# backplane_ethernet.net
KiCad netlist of a schematic drawn in Altium Designer
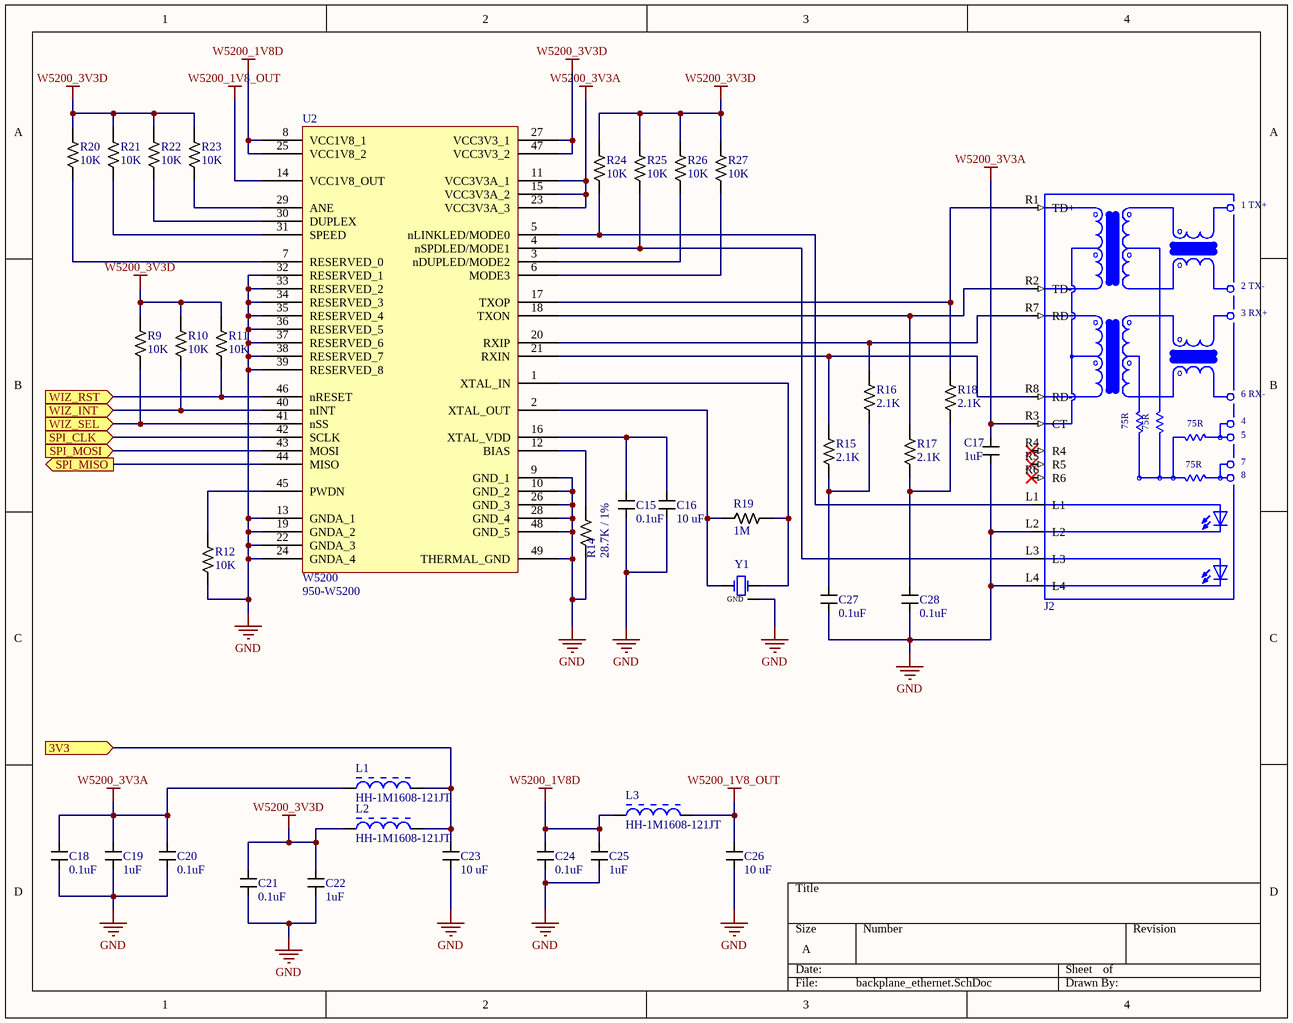
[diagram p0: backplane_ethernet.SchDoc]

(export (version "E")
  (design (tool "Eeschema 10.0.6"))
  (components
    (comp (ref "C15")
      (value "0.1uF")
      (footprint "CAPACITOR_0603")
      (description "Cap 100nF 6.3V +/-10%\r\nCeramic 0603")
      (fields
        (field (name "TOLERANCE") "+/- 10%")
        (field (name "VOLTAGE") "6.3V")
        (field (name "MADE BY") "Flip B")
      )
      (libsource (lib "Capacitors") (part "CAPACITOR_0.1uF_0603"))
    )
    (comp (ref "C16")
      (value "10uF Ceramic 6.3V")
      (footprint "CAPACITOR_0603")
      (description "Cap 10uF 6.3V +/-20%\r\nCeramic 0603")
      (fields
        (field (name "TOLERANCE") "+/- 20%")
        (field (name "VOLTAGE") "6.3V")
        (field (name "VALUE (UF)") "10 uF")
        (field (name "MADE BY") "Flip B")
      )
      (libsource (lib "Capacitors") (part "CAPACITOR_10uF_0603"))
    )
    (comp (ref "C17")
      (value "1uF")
      (footprint "CAPACITOR_0603")
      (description "Cap 1uF 16V +/-10%\r\nCeramic 0603")
      (fields
        (field (name "TOLERANCE") "+/- 10%")
        (field (name "VOLTAGE") "16V")
        (field (name "MADE BY") "Flip B")
      )
      (libsource (lib "Capacitors") (part "CAPACITOR_1uF_0603"))
    )
    (comp (ref "C18")
      (value "0.1uF")
      (footprint "CAPACITOR_0603")
      (description "Cap 100nF 6.3V +/-10%\r\nCeramic 0603")
      (fields
        (field (name "TOLERANCE") "+/- 10%")
        (field (name "VOLTAGE") "6.3V")
        (field (name "MADE BY") "Flip B")
      )
      (libsource (lib "Capacitors") (part "CAPACITOR_0.1uF_0603"))
    )
    (comp (ref "C19")
      (value "1uF")
      (footprint "CAPACITOR_0603")
      (description "Cap 1uF 16V +/-10%\r\nCeramic 0603")
      (fields
        (field (name "TOLERANCE") "+/- 10%")
        (field (name "VOLTAGE") "16V")
        (field (name "MADE BY") "Flip B")
      )
      (libsource (lib "Capacitors") (part "CAPACITOR_1uF_0603"))
    )
    (comp (ref "C20")
      (value "0.1uF")
      (footprint "CAPACITOR_0603")
      (description "Cap 100nF 6.3V +/-10%\r\nCeramic 0603")
      (fields
        (field (name "TOLERANCE") "+/- 10%")
        (field (name "VOLTAGE") "6.3V")
        (field (name "MADE BY") "Flip B")
      )
      (libsource (lib "Capacitors") (part "CAPACITOR_0.1uF_0603"))
    )
    (comp (ref "C21")
      (value "0.1uF")
      (footprint "CAPACITOR_0603")
      (description "Cap 100nF 6.3V +/-10%\r\nCeramic 0603")
      (fields
        (field (name "TOLERANCE") "+/- 10%")
        (field (name "VOLTAGE") "6.3V")
        (field (name "MADE BY") "Flip B")
      )
      (libsource (lib "Capacitors") (part "CAPACITOR_0.1uF_0603"))
    )
    (comp (ref "C22")
      (value "1uF")
      (footprint "CAPACITOR_0603")
      (description "Cap 1uF 16V +/-10%\r\nCeramic 0603")
      (fields
        (field (name "TOLERANCE") "+/- 10%")
        (field (name "VOLTAGE") "16V")
        (field (name "MADE BY") "Flip B")
      )
      (libsource (lib "Capacitors") (part "CAPACITOR_1uF_0603"))
    )
    (comp (ref "C23")
      (value "10uF Ceramic 6.3V")
      (footprint "CAPACITOR_0603")
      (description "Cap 10uF 6.3V +/-20%\r\nCeramic 0603")
      (fields
        (field (name "TOLERANCE") "+/- 20%")
        (field (name "VOLTAGE") "6.3V")
        (field (name "VALUE (UF)") "10 uF")
        (field (name "MADE BY") "Flip B")
      )
      (libsource (lib "Capacitors") (part "CAPACITOR_10uF_0603"))
    )
    (comp (ref "C24")
      (value "0.1uF")
      (footprint "CAPACITOR_0603")
      (description "Cap 100nF 6.3V +/-10%\r\nCeramic 0603")
      (fields
        (field (name "TOLERANCE") "+/- 10%")
        (field (name "VOLTAGE") "6.3V")
        (field (name "MADE BY") "Flip B")
      )
      (libsource (lib "Capacitors") (part "CAPACITOR_0.1uF_0603"))
    )
    (comp (ref "C25")
      (value "1uF")
      (footprint "CAPACITOR_0603")
      (description "Cap 1uF 16V +/-10%\r\nCeramic 0603")
      (fields
        (field (name "TOLERANCE") "+/- 10%")
        (field (name "VOLTAGE") "16V")
        (field (name "MADE BY") "Flip B")
      )
      (libsource (lib "Capacitors") (part "CAPACITOR_1uF_0603"))
    )
    (comp (ref "C26")
      (value "10uF Ceramic 6.3V")
      (footprint "CAPACITOR_0603")
      (description "Cap 10uF 6.3V +/-20%\r\nCeramic 0603")
      (fields
        (field (name "TOLERANCE") "+/- 20%")
        (field (name "VOLTAGE") "6.3V")
        (field (name "VALUE (UF)") "10 uF")
        (field (name "MADE BY") "Flip B")
      )
      (libsource (lib "Capacitors") (part "CAPACITOR_10uF_0603"))
    )
    (comp (ref "C27")
      (value "0.1uF")
      (footprint "CAPACITOR_0603")
      (description "Cap 100nF 6.3V +/-10%\r\nCeramic 0603")
      (fields
        (field (name "TOLERANCE") "+/- 10%")
        (field (name "VOLTAGE") "6.3V")
        (field (name "MADE BY") "Flip B")
      )
      (libsource (lib "Capacitors") (part "CAPACITOR_0.1uF_0603"))
    )
    (comp (ref "C28")
      (value "0.1uF")
      (footprint "CAPACITOR_0603")
      (description "Cap 100nF 6.3V +/-10%\r\nCeramic 0603")
      (fields
        (field (name "TOLERANCE") "+/- 10%")
        (field (name "VOLTAGE") "6.3V")
        (field (name "MADE BY") "Flip B")
      )
      (libsource (lib "Capacitors") (part "CAPACITOR_0.1uF_0603"))
    )
    (comp (ref "J2")
      (value "Ethernet Connector")
      (footprint "WIZNET_RB1-125BAG1A")
      (description "CONN JACK 1PORT 100 BASE-T PCB")
      (libsource (lib "Connectors") (part "RB1-125BAG1A"))
    )
    (comp (ref "L1")
      (value "HH-1M1608-121JT")
      (footprint "CTC-1608_L")
      (description "Chip Ferrite Bead, 0.14 Ohm, 1.1 A, -55 to 125 degC, 2-Pin SMD, RoHS, Tape and Reel")
      (fields (field (name "MANUFACTURER") "CTC Coils") (field (name "PARTNUMBER") "HH-1M1608"))
      (libsource (lib "Altium Content Vault") (part "IND-FB-2"))
    )
    (comp (ref "L2")
      (value "HH-1M1608-121JT")
      (footprint "CTC-1608_L")
      (description "Chip Ferrite Bead, 0.14 Ohm, 1.1 A, -55 to 125 degC, 2-Pin SMD, RoHS, Tape and Reel")
      (fields (field (name "MANUFACTURER") "CTC Coils") (field (name "PARTNUMBER") "HH-1M1608"))
      (libsource (lib "Altium Content Vault") (part "IND-FB-2"))
    )
    (comp (ref "L3")
      (value "HH-1M1608-121JT")
      (footprint "CTC-1608_L")
      (description "Chip Ferrite Bead, 0.14 Ohm, 1.1 A, -55 to 125 degC, 2-Pin SMD, RoHS, Tape and Reel")
      (fields (field (name "MANUFACTURER") "CTC Coils") (field (name "PARTNUMBER") "HH-1M1608"))
      (libsource (lib "Altium Content Vault") (part "IND-FB-2"))
    )
    (comp (ref "R9")
      (value "10k Ohm 5% 1/10W")
      (footprint "RESISTOR_0603")
      (description "RES 10k OHM 5% 1/10W 0603")
      (fields
        (field (name "TOLERANCE") "+/- 5%")
        (field (name "VALUE  (OHMS)") "10K")
        (field (name "MADE BY") "Robert Pafford")
      )
      (libsource (lib "Resistors") (part "RESISTOR_10K_0603"))
    )
    (comp (ref "R10")
      (value "10k Ohm 5% 1/10W")
      (footprint "RESISTOR_0603")
      (description "RES 10k OHM 5% 1/10W 0603")
      (fields
        (field (name "TOLERANCE") "+/- 5%")
        (field (name "VALUE  (OHMS)") "10K")
        (field (name "MADE BY") "Robert Pafford")
      )
      (libsource (lib "Resistors") (part "RESISTOR_10K_0603"))
    )
    (comp (ref "R11")
      (value "10k Ohm 5% 1/10W")
      (footprint "RESISTOR_0603")
      (description "RES 10k OHM 5% 1/10W 0603")
      (fields
        (field (name "TOLERANCE") "+/- 5%")
        (field (name "VALUE  (OHMS)") "10K")
        (field (name "MADE BY") "Robert Pafford")
      )
      (libsource (lib "Resistors") (part "RESISTOR_10K_0603"))
    )
    (comp (ref "R12")
      (value "10k Ohm 5% 1/10W")
      (footprint "RESISTOR_0603")
      (description "RES 10k OHM 5% 1/10W 0603")
      (fields
        (field (name "TOLERANCE") "+/- 5%")
        (field (name "VALUE  (OHMS)") "10K")
        (field (name "MADE BY") "Robert Pafford")
      )
      (libsource (lib "Resistors") (part "RESISTOR_10K_0603"))
    )
    (comp (ref "R14")
      (value "K / 1%")
      (footprint "RESISTOR_0603")
      (description "RES 28.7K OHM 1% 1/8W 0603")
      (fields
        (field (name "TOLERANCE") "+/- 5%")
        (field (name "VALUE  (OHMS)") "28.7K / 1%")
        (field (name "MADE BY") "Robert Pafford")
      )
      (libsource (lib "Resistors") (part "RESISTOR_28.7K / 1%_0603_1"))
    )
    (comp (ref "R15")
      (value "2.1k Ohm 5% 1/8W")
      (footprint "RESISTOR_0603")
      (description "RES 2.1k OHM 5% 1/8W 0603")
      (fields
        (field (name "TOLERANCE") "+/- 5%")
        (field (name "VALUE  (OHMS)") "2.1K")
        (field (name "MADE BY") "Robert Pafford")
      )
      (libsource (lib "Resistors") (part "RESISTOR_2.1K_0603_1"))
    )
    (comp (ref "R16")
      (value "2.1k Ohm 5% 1/8W")
      (footprint "RESISTOR_0603")
      (description "RES 2.1k OHM 5% 1/8W 0603")
      (fields
        (field (name "TOLERANCE") "+/- 5%")
        (field (name "VALUE  (OHMS)") "2.1K")
        (field (name "MADE BY") "Robert Pafford")
      )
      (libsource (lib "Resistors") (part "RESISTOR_2.1K_0603_1"))
    )
    (comp (ref "R17")
      (value "2.1k Ohm 5% 1/8W")
      (footprint "RESISTOR_0603")
      (description "RES 2.1k OHM 5% 1/8W 0603")
      (fields
        (field (name "TOLERANCE") "+/- 5%")
        (field (name "VALUE  (OHMS)") "2.1K")
        (field (name "MADE BY") "Robert Pafford")
      )
      (libsource (lib "Resistors") (part "RESISTOR_2.1K_0603_1"))
    )
    (comp (ref "R18")
      (value "2.1k Ohm 5% 1/8W")
      (footprint "RESISTOR_0603")
      (description "RES 2.1k OHM 5% 1/8W 0603")
      (fields
        (field (name "TOLERANCE") "+/- 5%")
        (field (name "VALUE  (OHMS)") "2.1K")
        (field (name "MADE BY") "Robert Pafford")
      )
      (libsource (lib "Resistors") (part "RESISTOR_2.1K_0603_1"))
    )
    (comp (ref "R19")
      (value "1M")
      (footprint "RESISTOR_0603")
      (description "RES 1M OHM 1/8W 0603")
      (fields
        (field (name "TOLERANCE") "+/- 5%")
        (field (name "VALUE  (OHMS)") "1M")
        (field (name "MADE BY") "Robert Pafford")
      )
      (libsource (lib "Resistors") (part "RESISTOR_1M_0603_1"))
    )
    (comp (ref "R20")
      (value "10k Ohm 5% 1/10W")
      (footprint "RESISTOR_0603")
      (description "RES 10k OHM 5% 1/10W 0603")
      (fields
        (field (name "TOLERANCE") "+/- 5%")
        (field (name "VALUE  (OHMS)") "10K")
        (field (name "MADE BY") "Robert Pafford")
      )
      (libsource (lib "Resistors") (part "RESISTOR_10K_0603"))
    )
    (comp (ref "R21")
      (value "10k Ohm 5% 1/10W")
      (footprint "RESISTOR_0603")
      (description "RES 10k OHM 5% 1/10W 0603")
      (fields
        (field (name "TOLERANCE") "+/- 5%")
        (field (name "VALUE  (OHMS)") "10K")
        (field (name "MADE BY") "Robert Pafford")
      )
      (libsource (lib "Resistors") (part "RESISTOR_10K_0603"))
    )
    (comp (ref "R22")
      (value "10k Ohm 5% 1/10W")
      (footprint "RESISTOR_0603")
      (description "RES 10k OHM 5% 1/10W 0603")
      (fields
        (field (name "TOLERANCE") "+/- 5%")
        (field (name "VALUE  (OHMS)") "10K")
        (field (name "MADE BY") "Robert Pafford")
      )
      (libsource (lib "Resistors") (part "RESISTOR_10K_0603"))
    )
    (comp (ref "R23")
      (value "10k Ohm 5% 1/10W")
      (footprint "RESISTOR_0603")
      (description "RES 10k OHM 5% 1/10W 0603")
      (fields
        (field (name "TOLERANCE") "+/- 5%")
        (field (name "VALUE  (OHMS)") "10K")
        (field (name "MADE BY") "Robert Pafford")
      )
      (libsource (lib "Resistors") (part "RESISTOR_10K_0603"))
    )
    (comp (ref "R24")
      (value "10k Ohm 5% 1/10W")
      (footprint "RESISTOR_0603")
      (description "RES 10k OHM 5% 1/10W 0603")
      (fields
        (field (name "TOLERANCE") "+/- 5%")
        (field (name "VALUE  (OHMS)") "10K")
        (field (name "MADE BY") "Robert Pafford")
      )
      (libsource (lib "Resistors") (part "RESISTOR_10K_0603"))
    )
    (comp (ref "R25")
      (value "10k Ohm 5% 1/10W")
      (footprint "RESISTOR_0603")
      (description "RES 10k OHM 5% 1/10W 0603")
      (fields
        (field (name "TOLERANCE") "+/- 5%")
        (field (name "VALUE  (OHMS)") "10K")
        (field (name "MADE BY") "Robert Pafford")
      )
      (libsource (lib "Resistors") (part "RESISTOR_10K_0603"))
    )
    (comp (ref "R26")
      (value "10k Ohm 5% 1/10W")
      (footprint "RESISTOR_0603")
      (description "RES 10k OHM 5% 1/10W 0603")
      (fields
        (field (name "TOLERANCE") "+/- 5%")
        (field (name "VALUE  (OHMS)") "10K")
        (field (name "MADE BY") "Robert Pafford")
      )
      (libsource (lib "Resistors") (part "RESISTOR_10K_0603"))
    )
    (comp (ref "R27")
      (value "10k Ohm 5% 1/10W")
      (footprint "RESISTOR_0603")
      (description "RES 10k OHM 5% 1/10W 0603")
      (fields
        (field (name "TOLERANCE") "+/- 5%")
        (field (name "VALUE  (OHMS)") "10K")
        (field (name "MADE BY") "Robert Pafford")
      )
      (libsource (lib "Resistors") (part "RESISTOR_10K_0603"))
    )
    (comp (ref "U2")
      (value "W5200")
      (footprint "QFN-48")
      (description "WIZNET W5200\r\n48QFN (7x7 mm)")
      (fields
        (field (name "MF") "Texas Instruments")
        (field (name "MP") "LM1117IMPX-3.3/NOPB")
        (field (name "SUPPLIER PART NUMBER 1") "950-W5200")
        (field (name "CREATED BY:") "Siddharth.V")
      )
      (libsource (lib "Integrated Circuits") (part "W5200"))
    )
    (comp (ref "Y1")
      (value "CRYSTAL 25.0000MHZ 18PF SMD")
      (footprint "4-SMD No Lead Crystal")
      (description "25 MHz ±20ppm Crystal 18pF")
      (fields (field (name "MADE BY") "Robert Pafford"))
      (libsource (lib "Crystals") (part "CRYSTAL_25MHz_SMD_1"))
    )
  )
  (nets
    (net (code "1") (name "/3V3") (class "Default")
      (node (ref "C23") (pin "1") (pinfunction "1_1") (pintype "passive"))
      (node (ref "L1") (pin "2") (pinfunction "2_2") (pintype "passive"))
      (node (ref "L2") (pin "2") (pinfunction "2_2") (pintype "passive"))
    )
    (net (code "2") (name "/SPI_CLK") (class "Default")
      (node (ref "U2") (pin "42") (pinfunction "SCLK_42") (pintype "passive"))
    )
    (net (code "3") (name "/SPI_MISO") (class "Default")
      (node (ref "U2") (pin "44") (pinfunction "MISO_44") (pintype "passive"))
    )
    (net (code "4") (name "/SPI_MOSI") (class "Default")
      (node (ref "U2") (pin "43") (pinfunction "MOSI_43") (pintype "passive"))
    )
    (net (code "5") (name "/WIZ_INT") (class "Default")
      (node (ref "R10") (pin "2") (pinfunction "2_2") (pintype "passive"))
      (node (ref "U2") (pin "40") (pinfunction "nINT_40") (pintype "passive"))
    )
    (net (code "6") (name "/WIZ_RST") (class "Default")
      (node (ref "R11") (pin "2") (pinfunction "2_2") (pintype "passive"))
      (node (ref "U2") (pin "46") (pinfunction "nRESET_46") (pintype "passive"))
    )
    (net (code "7") (name "/WIZ_SEL") (class "Default")
      (node (ref "R9") (pin "2") (pinfunction "2_2") (pintype "passive"))
      (node (ref "U2") (pin "41") (pinfunction "nSS_41") (pintype "passive"))
    )
    (net (code "8") (name "GND") (class "Default")
      (node (ref "C15") (pin "2") (pinfunction "2_2") (pintype "passive"))
      (node (ref "C16") (pin "2") (pinfunction "2_2") (pintype "passive"))
      (node (ref "C17") (pin "2") (pinfunction "2_2") (pintype "passive"))
      (node (ref "C18") (pin "2") (pinfunction "2_2") (pintype "passive"))
      (node (ref "C19") (pin "2") (pinfunction "2_2") (pintype "passive"))
      (node (ref "C20") (pin "2") (pinfunction "2_2") (pintype "passive"))
      (node (ref "C21") (pin "2") (pinfunction "2_2") (pintype "passive"))
      (node (ref "C22") (pin "2") (pinfunction "2_2") (pintype "passive"))
      (node (ref "C23") (pin "2") (pinfunction "2_2") (pintype "passive"))
      (node (ref "C24") (pin "2") (pinfunction "2_2") (pintype "passive"))
      (node (ref "C25") (pin "2") (pinfunction "2_2") (pintype "passive"))
      (node (ref "C26") (pin "2") (pinfunction "2_2") (pintype "passive"))
      (node (ref "C27") (pin "2") (pinfunction "2_2") (pintype "passive"))
      (node (ref "C28") (pin "2") (pinfunction "2_2") (pintype "passive"))
      (node (ref "J2") (pin "L2") (pinfunction "L2_L2") (pintype "passive"))
      (node (ref "J2") (pin "L4") (pinfunction "L4_L4") (pintype "passive"))
      (node (ref "R12") (pin "2") (pinfunction "2_2") (pintype "passive"))
      (node (ref "R14") (pin "2") (pinfunction "2_2") (pintype "passive"))
      (node (ref "U2") (pin "10") (pinfunction "GND_2_10") (pintype "passive"))
      (node (ref "U2") (pin "13") (pinfunction "GNDA_1_13") (pintype "passive"))
      (node (ref "U2") (pin "19") (pinfunction "GNDA_2_19") (pintype "passive"))
      (node (ref "U2") (pin "22") (pinfunction "GNDA_3_22") (pintype "passive"))
      (node (ref "U2") (pin "24") (pinfunction "GNDA_4_24") (pintype "passive"))
      (node (ref "U2") (pin "26") (pinfunction "GND_3_26") (pintype "passive"))
      (node (ref "U2") (pin "28") (pinfunction "GND_4_28") (pintype "passive"))
      (node (ref "U2") (pin "32") (pinfunction "RESERVED_1_32") (pintype "passive"))
      (node (ref "U2") (pin "33") (pinfunction "RESERVED_2_33") (pintype "passive"))
      (node (ref "U2") (pin "34") (pinfunction "RESERVED_3_34") (pintype "passive"))
      (node (ref "U2") (pin "35") (pinfunction "RESERVED_4_35") (pintype "passive"))
      (node (ref "U2") (pin "36") (pinfunction "RESERVED_5_36") (pintype "passive"))
      (node (ref "U2") (pin "37") (pinfunction "RESERVED_6_37") (pintype "passive"))
      (node (ref "U2") (pin "38") (pinfunction "RESERVED_7_38") (pintype "passive"))
      (node (ref "U2") (pin "39") (pinfunction "RESERVED_8_39") (pintype "passive"))
      (node (ref "U2") (pin "48") (pinfunction "GND_5_48") (pintype "passive"))
      (node (ref "U2") (pin "49") (pinfunction "THERMAL_GND_49") (pintype "passive"))
      (node (ref "U2") (pin "9") (pinfunction "GND_1_9") (pintype "passive"))
      (node (ref "Y1") (pin "GND") (pinfunction "GND_GND") (pintype "power_in"))
    )
    (net (code "9") (name "Net-(C27-Pad1)") (class "Default")
      (node (ref "C27") (pin "1") (pinfunction "1_1") (pintype "passive"))
      (node (ref "R15") (pin "2") (pinfunction "2_2") (pintype "passive"))
      (node (ref "R16") (pin "2") (pinfunction "2_2") (pintype "passive"))
    )
    (net (code "10") (name "Net-(C28-Pad1)") (class "Default")
      (node (ref "C28") (pin "1") (pinfunction "1_1") (pintype "passive"))
      (node (ref "R17") (pin "2") (pinfunction "2_2") (pintype "passive"))
      (node (ref "R18") (pin "2") (pinfunction "2_2") (pintype "passive"))
    )
    (net (code "11") (name "Net-(J2-RD+)") (class "Default")
      (node (ref "J2") (pin "R7") (pinfunction "RD+_R7") (pintype "input"))
      (node (ref "R16") (pin "1") (pinfunction "1_1") (pintype "passive"))
      (node (ref "U2") (pin "20") (pinfunction "RXIP_20") (pintype "passive"))
    )
    (net (code "12") (name "Net-(J2-RD-)") (class "Default")
      (node (ref "J2") (pin "R8") (pinfunction "RD-_R8") (pintype "input"))
      (node (ref "R15") (pin "1") (pinfunction "1_1") (pintype "passive"))
      (node (ref "U2") (pin "21") (pinfunction "RXIN_21") (pintype "passive"))
    )
    (net (code "13") (name "Net-(J2-TD+)") (class "Default")
      (node (ref "J2") (pin "R1") (pinfunction "TD+_R1") (pintype "input"))
      (node (ref "R18") (pin "1") (pinfunction "1_1") (pintype "passive"))
      (node (ref "U2") (pin "17") (pinfunction "TXOP_17") (pintype "passive"))
    )
    (net (code "14") (name "Net-(J2-TD-)") (class "Default")
      (node (ref "J2") (pin "R2") (pinfunction "TD-_R2") (pintype "input"))
      (node (ref "R17") (pin "1") (pinfunction "1_1") (pintype "passive"))
      (node (ref "U2") (pin "18") (pinfunction "TXON_18") (pintype "passive"))
    )
    (net (code "15") (name "Net-(U2-ANE)") (class "Default")
      (node (ref "R23") (pin "2") (pinfunction "2_2") (pintype "passive"))
      (node (ref "U2") (pin "29") (pinfunction "ANE_29") (pintype "passive"))
    )
    (net (code "16") (name "Net-(U2-BIAS)") (class "Default")
      (node (ref "R14") (pin "1") (pinfunction "1_1") (pintype "passive"))
      (node (ref "U2") (pin "12") (pinfunction "BIAS_12") (pintype "passive"))
    )
    (net (code "17") (name "Net-(U2-DUPLEX)") (class "Default")
      (node (ref "R22") (pin "2") (pinfunction "2_2") (pintype "passive"))
      (node (ref "U2") (pin "30") (pinfunction "DUPLEX_30") (pintype "passive"))
    )
    (net (code "18") (name "Net-(U2-MODE3)") (class "Default")
      (node (ref "R27") (pin "2") (pinfunction "2_2") (pintype "passive"))
      (node (ref "U2") (pin "6") (pinfunction "MODE3_6") (pintype "passive"))
    )
    (net (code "19") (name "Net-(U2-PWDN)") (class "Default")
      (node (ref "R12") (pin "1") (pinfunction "1_1") (pintype "passive"))
      (node (ref "U2") (pin "45") (pinfunction "PWDN_45") (pintype "passive"))
    )
    (net (code "20") (name "Net-(U2-RESERVED_0)") (class "Default")
      (node (ref "R20") (pin "2") (pinfunction "2_2") (pintype "passive"))
      (node (ref "U2") (pin "7") (pinfunction "RESERVED_0_7") (pintype "passive"))
    )
    (net (code "21") (name "Net-(U2-SPEED)") (class "Default")
      (node (ref "R21") (pin "2") (pinfunction "2_2") (pintype "passive"))
      (node (ref "U2") (pin "31") (pinfunction "SPEED_31") (pintype "passive"))
    )
    (net (code "22") (name "Net-(U2-XTAL_IN)") (class "Default")
      (node (ref "R19") (pin "1") (pinfunction "1_1") (pintype "passive"))
      (node (ref "U2") (pin "1") (pinfunction "XTAL_IN_1") (pintype "passive"))
      (node (ref "Y1") (pin "2") (pinfunction "2_2") (pintype "passive"))
    )
    (net (code "23") (name "Net-(U2-XTAL_OUT)") (class "Default")
      (node (ref "R19") (pin "2") (pinfunction "2_2") (pintype "passive"))
      (node (ref "U2") (pin "2") (pinfunction "XTAL_OUT_2") (pintype "passive"))
      (node (ref "Y1") (pin "1") (pinfunction "1_1") (pintype "passive"))
    )
    (net (code "24") (name "Net-(U2-XTAL_VDD)") (class "Default")
      (node (ref "C15") (pin "1") (pinfunction "1_1") (pintype "passive"))
      (node (ref "C16") (pin "1") (pinfunction "1_1") (pintype "passive"))
      (node (ref "U2") (pin "16") (pinfunction "XTAL_VDD_16") (pintype "passive"))
    )
    (net (code "25") (name "Net-(U2-nDUPLED{slash}MODE2)") (class "Default")
      (node (ref "R26") (pin "2") (pinfunction "2_2") (pintype "passive"))
      (node (ref "U2") (pin "3") (pinfunction "nDUPLED/MODE2_3") (pintype "passive"))
    )
    (net (code "26") (name "Net-(U2-nLINKLED{slash}MODE0)") (class "Default")
      (node (ref "J2") (pin "L1") (pinfunction "L1_L1") (pintype "passive"))
      (node (ref "R24") (pin "2") (pinfunction "2_2") (pintype "passive"))
      (node (ref "U2") (pin "5") (pinfunction "nLINKLED/MODE0_5") (pintype "passive"))
    )
    (net (code "27") (name "Net-(U2-nSPDLED{slash}MODE1)") (class "Default")
      (node (ref "J2") (pin "L3") (pinfunction "L3_L3") (pintype "passive"))
      (node (ref "R25") (pin "2") (pinfunction "2_2") (pintype "passive"))
      (node (ref "U2") (pin "4") (pinfunction "nSPDLED/MODE1_4") (pintype "passive"))
    )
    (net (code "28") (name "W5200_1V8D") (class "Default")
      (node (ref "C24") (pin "1") (pinfunction "1_1") (pintype "passive"))
      (node (ref "C25") (pin "1") (pinfunction "1_1") (pintype "passive"))
      (node (ref "L3") (pin "1") (pinfunction "1_1") (pintype "passive"))
      (node (ref "U2") (pin "25") (pinfunction "VCC1V8_2_25") (pintype "passive"))
      (node (ref "U2") (pin "8") (pinfunction "VCC1V8_1_8") (pintype "passive"))
    )
    (net (code "29") (name "W5200_1V8_OUT") (class "Default")
      (node (ref "C26") (pin "1") (pinfunction "1_1") (pintype "passive"))
      (node (ref "L3") (pin "2") (pinfunction "2_2") (pintype "passive"))
      (node (ref "U2") (pin "14") (pinfunction "VCC1V8_OUT_14") (pintype "passive"))
    )
    (net (code "30") (name "W5200_3V3A") (class "Default")
      (node (ref "C17") (pin "1") (pinfunction "1_1") (pintype "passive"))
      (node (ref "C18") (pin "1") (pinfunction "1_1") (pintype "passive"))
      (node (ref "C19") (pin "1") (pinfunction "1_1") (pintype "passive"))
      (node (ref "C20") (pin "1") (pinfunction "1_1") (pintype "passive"))
      (node (ref "J2") (pin "R3") (pinfunction "CT_R3") (pintype "input"))
      (node (ref "L1") (pin "1") (pinfunction "1_1") (pintype "passive"))
      (node (ref "U2") (pin "11") (pinfunction "VCC3V3A_1_11") (pintype "passive"))
      (node (ref "U2") (pin "15") (pinfunction "VCC3V3A_2_15") (pintype "passive"))
      (node (ref "U2") (pin "23") (pinfunction "VCC3V3A_3_23") (pintype "passive"))
    )
    (net (code "31") (name "W5200_3V3D") (class "Default")
      (node (ref "C21") (pin "1") (pinfunction "1_1") (pintype "passive"))
      (node (ref "C22") (pin "1") (pinfunction "1_1") (pintype "passive"))
      (node (ref "L2") (pin "1") (pinfunction "1_1") (pintype "passive"))
      (node (ref "R10") (pin "1") (pinfunction "1_1") (pintype "passive"))
      (node (ref "R11") (pin "1") (pinfunction "1_1") (pintype "passive"))
      (node (ref "R20") (pin "1") (pinfunction "1_1") (pintype "passive"))
      (node (ref "R21") (pin "1") (pinfunction "1_1") (pintype "passive"))
      (node (ref "R22") (pin "1") (pinfunction "1_1") (pintype "passive"))
      (node (ref "R23") (pin "1") (pinfunction "1_1") (pintype "passive"))
      (node (ref "R24") (pin "1") (pinfunction "1_1") (pintype "passive"))
      (node (ref "R25") (pin "1") (pinfunction "1_1") (pintype "passive"))
      (node (ref "R26") (pin "1") (pinfunction "1_1") (pintype "passive"))
      (node (ref "R27") (pin "1") (pinfunction "1_1") (pintype "passive"))
      (node (ref "R9") (pin "1") (pinfunction "1_1") (pintype "passive"))
      (node (ref "U2") (pin "27") (pinfunction "VCC3V3_1_27") (pintype "passive"))
      (node (ref "U2") (pin "47") (pinfunction "VCC3V3_2_47") (pintype "passive"))
    )
    (net (code "32") (name "unconnected-(J2-PadR4)") (class "Default")
      (node (ref "J2") (pin "R4") (pinfunction "R4_R4") (pintype "input+no_connect"))
    )
    (net (code "33") (name "unconnected-(J2-PadR5)") (class "Default")
      (node (ref "J2") (pin "R5") (pinfunction "R5_R5") (pintype "input+no_connect"))
    )
    (net (code "34") (name "unconnected-(J2-PadR6)") (class "Default")
      (node (ref "J2") (pin "R6") (pinfunction "R6_R6") (pintype "input+no_connect"))
    )
  )
)
